# primobot.net
KiCad netlist of a schematic drawn in EAGLE
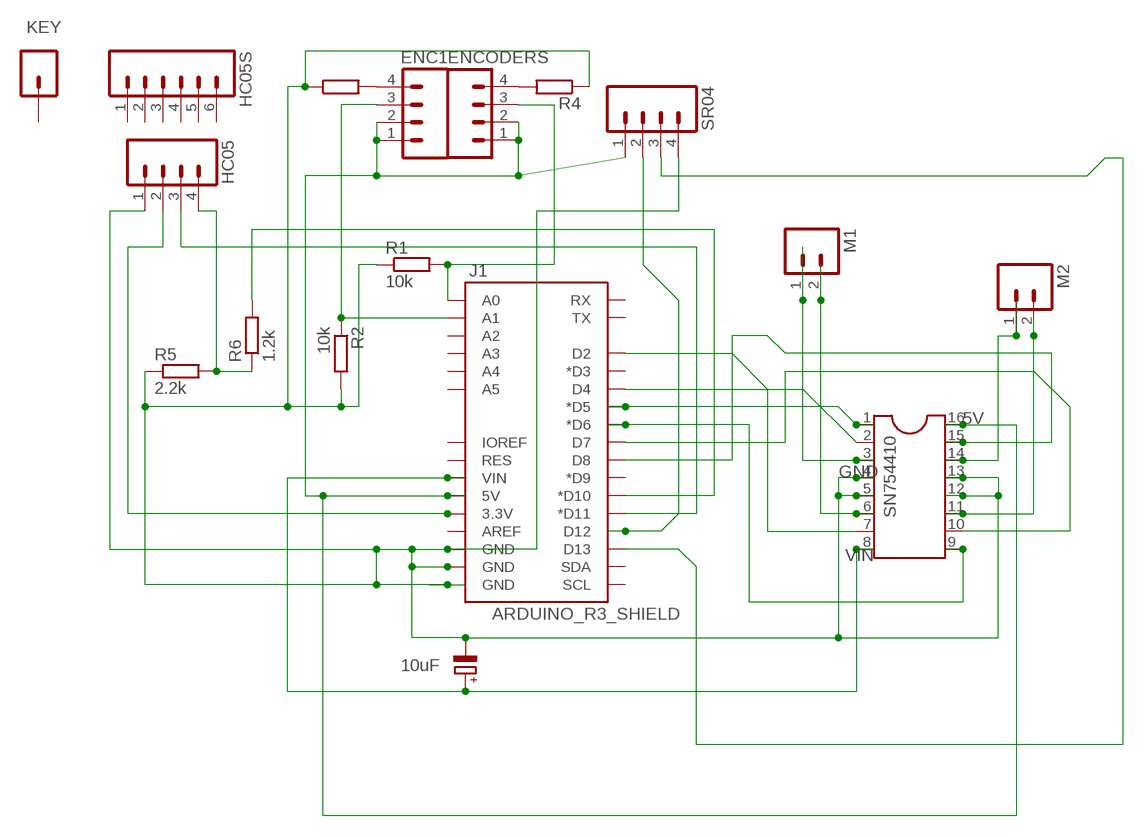
[diagram p0: schematic, sheet 1]

(export (version "E")
  (design (tool "Eeschema 10.0.6"))
  (components
    (comp (ref "C1")
      (value "10uF")
      (footprint "eagle-import:E5-10,5")
      (libsource (lib "eagle-import") (part "CPOL-EUE5-10.5"))
    )
    (comp (ref "ENC1")
      (value "M04PTH")
      (footprint "eagle-import:1X04")
      (libsource (lib "eagle-import") (part "M04PTH"))
    )
    (comp (ref "ENCODERS")
      (value "M04PTH")
      (footprint "eagle-import:1X04")
      (libsource (lib "eagle-import") (part "M04PTH"))
    )
    (comp (ref "HC05")
      (value "M04PTH")
      (footprint "eagle-import:1X04")
      (libsource (lib "eagle-import") (part "M04PTH"))
    )
    (comp (ref "HC05S")
      (value "M06SILK_FEMALE_PTH")
      (footprint "eagle-import:1X06")
      (libsource (lib "eagle-import") (part "M06SILK_FEMALE_PTH"))
    )
    (comp (ref "J1")
      (value "ARDUINO_R3_SHIELD")
      (footprint "eagle-import:UNO_R3_SHIELD")
      (libsource (lib "eagle-import") (part "ARDUINO_R3_SHIELD"))
    )
    (comp (ref "KEY")
      (value "M01PTH")
      (footprint "eagle-import:1X01")
      (libsource (lib "eagle-import") (part "M01PTH"))
    )
    (comp (ref "M1")
      (value "M02PTH")
      (footprint "eagle-import:1X02")
      (libsource (lib "eagle-import") (part "M02PTH"))
    )
    (comp (ref "M2")
      (value "M02PTH")
      (footprint "eagle-import:1X02")
      (libsource (lib "eagle-import") (part "M02PTH"))
    )
    (comp (ref "R1")
      (value "10k")
      (footprint "eagle-import:0207_10")
      (libsource (lib "eagle-import") (part "R-EU_0207/10"))
    )
    (comp (ref "R2")
      (value "10k")
      (footprint "eagle-import:0207_10")
      (libsource (lib "eagle-import") (part "R-EU_0207/10"))
    )
    (comp (ref "R3")
      (value "R-EU_0207/10")
      (footprint "eagle-import:0207_10")
      (libsource (lib "eagle-import") (part "R-EU_0207/10"))
    )
    (comp (ref "R4")
      (value "R-EU_0207/10")
      (footprint "eagle-import:0207_10")
      (libsource (lib "eagle-import") (part "R-EU_0207/10"))
    )
    (comp (ref "R5")
      (value "2.2k")
      (footprint "eagle-import:0207_10")
      (libsource (lib "eagle-import") (part "R-EU_0207/10"))
    )
    (comp (ref "R6")
      (value "1.2k")
      (footprint "eagle-import:0207_10")
      (libsource (lib "eagle-import") (part "R-EU_0207/10"))
    )
    (comp (ref "SN754410")
      (value "DIL16S")
      (footprint "eagle-import:SOCKET-16")
      (libsource (lib "eagle-import") (part "DIL16S"))
    )
    (comp (ref "SR04")
      (value "M04PTH")
      (footprint "eagle-import:1X04")
      (libsource (lib "eagle-import") (part "M04PTH"))
    )
  )
  (nets
    (net (code "1") (name "/5V") (class "Default")
      (node (ref "ENC1") (pin "1") (pinfunction "1_1") (pintype "passive"))
      (node (ref "ENC1") (pin "2") (pinfunction "2_2") (pintype "passive"))
      (node (ref "ENCODERS") (pin "1") (pinfunction "1_1") (pintype "passive"))
      (node (ref "ENCODERS") (pin "2") (pinfunction "2_2") (pintype "passive"))
      (node (ref "J1") (pin "5V") (pinfunction "5V_5V") (pintype "bidirectional"))
      (node (ref "SN754410") (pin "16") (pinfunction "16_16") (pintype "passive"))
      (node (ref "SR04") (pin "1") (pinfunction "1_1") (pintype "passive"))
    )
    (net (code "2") (name "/GND") (class "Default")
      (node (ref "C1") (pin "-") (pinfunction "-_-") (pintype "passive"))
      (node (ref "HC05") (pin "1") (pinfunction "1_1") (pintype "passive"))
      (node (ref "J1") (pin "GND@0") (pinfunction "GND_GND@0") (pintype "bidirectional"))
      (node (ref "J1") (pin "GND@1") (pinfunction "GND_GND@1") (pintype "bidirectional"))
      (node (ref "J1") (pin "GND@2") (pinfunction "GND_GND@2") (pintype "bidirectional"))
      (node (ref "R1") (pin "1") (pinfunction "1_1") (pintype "passive"))
      (node (ref "R2") (pin "2") (pinfunction "2_2") (pintype "passive"))
      (node (ref "R3") (pin "1") (pinfunction "1_1") (pintype "passive"))
      (node (ref "R4") (pin "1") (pinfunction "1_1") (pintype "passive"))
      (node (ref "R5") (pin "1") (pinfunction "1_1") (pintype "passive"))
      (node (ref "SN754410") (pin "12") (pinfunction "12_12") (pintype "passive"))
      (node (ref "SN754410") (pin "13") (pinfunction "13_13") (pintype "passive"))
      (node (ref "SN754410") (pin "4") (pinfunction "4_4") (pintype "passive"))
      (node (ref "SN754410") (pin "5") (pinfunction "5_5") (pintype "passive"))
      (node (ref "SR04") (pin "4") (pinfunction "4_4") (pintype "passive"))
    )
    (net (code "3") (name "/VIN") (class "Default")
      (node (ref "C1") (pin "+") (pinfunction "+_+") (pintype "passive"))
      (node (ref "J1") (pin "VIN") (pinfunction "VIN_VIN") (pintype "bidirectional"))
      (node (ref "SN754410") (pin "8") (pinfunction "8_8") (pintype "passive"))
    )
    (net (code "4") (name "Net-(ENC1-Pad3)") (class "Default")
      (node (ref "ENC1") (pin "3") (pinfunction "3_3") (pintype "passive"))
      (node (ref "J1") (pin "A1") (pinfunction "A1_A1") (pintype "bidirectional"))
      (node (ref "R2") (pin "1") (pinfunction "1_1") (pintype "passive"))
    )
    (net (code "5") (name "Net-(ENC1-Pad4)") (class "Default")
      (node (ref "ENC1") (pin "4") (pinfunction "4_4") (pintype "passive"))
      (node (ref "R3") (pin "2") (pinfunction "2_2") (pintype "passive"))
    )
    (net (code "6") (name "Net-(ENCODERS-Pad3)") (class "Default")
      (node (ref "ENCODERS") (pin "3") (pinfunction "3_3") (pintype "passive"))
      (node (ref "J1") (pin "A0") (pinfunction "A0_A0") (pintype "bidirectional"))
      (node (ref "R1") (pin "2") (pinfunction "2_2") (pintype "passive"))
    )
    (net (code "7") (name "Net-(ENCODERS-Pad4)") (class "Default")
      (node (ref "ENCODERS") (pin "4") (pinfunction "4_4") (pintype "passive"))
      (node (ref "R4") (pin "2") (pinfunction "2_2") (pintype "passive"))
    )
    (net (code "8") (name "Net-(HC05-Pad2)") (class "Default")
      (node (ref "HC05") (pin "2") (pinfunction "2_2") (pintype "passive"))
      (node (ref "J1") (pin "3.3V") (pinfunction "3.3V_3.3V") (pintype "bidirectional"))
    )
    (net (code "9") (name "Net-(HC05-Pad4)") (class "Default")
      (node (ref "HC05") (pin "4") (pinfunction "4_4") (pintype "passive"))
      (node (ref "R5") (pin "2") (pinfunction "2_2") (pintype "passive"))
      (node (ref "R6") (pin "1") (pinfunction "1_1") (pintype "passive"))
    )
    (net (code "10") (name "Net-(J1-*D5)") (class "Default")
      (node (ref "J1") (pin "D5") (pinfunction "*D5_D5") (pintype "bidirectional"))
      (node (ref "SN754410") (pin "1") (pinfunction "1_1") (pintype "passive"))
    )
    (net (code "11") (name "Net-(J1-*D6)") (class "Default")
      (node (ref "J1") (pin "D6") (pinfunction "*D6_D6") (pintype "bidirectional"))
      (node (ref "SN754410") (pin "9") (pinfunction "9_9") (pintype "passive"))
    )
    (net (code "12") (name "Net-(J1-*D10)") (class "Default")
      (node (ref "J1") (pin "D10") (pinfunction "*D10_D10") (pintype "bidirectional"))
      (node (ref "R6") (pin "2") (pinfunction "2_2") (pintype "passive"))
    )
    (net (code "13") (name "Net-(J1-*D11)") (class "Default")
      (node (ref "HC05") (pin "3") (pinfunction "3_3") (pintype "passive"))
      (node (ref "J1") (pin "D11") (pinfunction "*D11_D11") (pintype "bidirectional"))
    )
    (net (code "14") (name "Net-(J1-PadD2)") (class "Default")
      (node (ref "J1") (pin "D2") (pinfunction "D2_D2") (pintype "bidirectional"))
      (node (ref "SN754410") (pin "7") (pinfunction "7_7") (pintype "passive"))
    )
    (net (code "15") (name "Net-(J1-PadD4)") (class "Default")
      (node (ref "J1") (pin "D4") (pinfunction "D4_D4") (pintype "bidirectional"))
      (node (ref "SN754410") (pin "2") (pinfunction "2_2") (pintype "passive"))
    )
    (net (code "16") (name "Net-(J1-PadD7)") (class "Default")
      (node (ref "J1") (pin "D7") (pinfunction "D7_D7") (pintype "bidirectional"))
      (node (ref "SN754410") (pin "10") (pinfunction "10_10") (pintype "passive"))
    )
    (net (code "17") (name "Net-(J1-PadD8)") (class "Default")
      (node (ref "J1") (pin "D8") (pinfunction "D8_D8") (pintype "bidirectional"))
      (node (ref "SN754410") (pin "15") (pinfunction "15_15") (pintype "passive"))
    )
    (net (code "18") (name "Net-(J1-PadD12)") (class "Default")
      (node (ref "J1") (pin "D12") (pinfunction "D12_D12") (pintype "bidirectional"))
      (node (ref "SR04") (pin "2") (pinfunction "2_2") (pintype "passive"))
    )
    (net (code "19") (name "Net-(J1-PadD13)") (class "Default")
      (node (ref "J1") (pin "D13") (pinfunction "D13_D13") (pintype "bidirectional"))
      (node (ref "SR04") (pin "3") (pinfunction "3_3") (pintype "passive"))
    )
    (net (code "20") (name "Net-(M1-Pad1)") (class "Default")
      (node (ref "M1") (pin "1") (pinfunction "1_1") (pintype "passive"))
      (node (ref "SN754410") (pin "3") (pinfunction "3_3") (pintype "passive"))
    )
    (net (code "21") (name "Net-(M1-Pad2)") (class "Default")
      (node (ref "M1") (pin "2") (pinfunction "2_2") (pintype "passive"))
      (node (ref "SN754410") (pin "6") (pinfunction "6_6") (pintype "passive"))
    )
    (net (code "22") (name "Net-(M2-Pad1)") (class "Default")
      (node (ref "M2") (pin "1") (pinfunction "1_1") (pintype "passive"))
      (node (ref "SN754410") (pin "14") (pinfunction "14_14") (pintype "passive"))
    )
    (net (code "23") (name "Net-(M2-Pad2)") (class "Default")
      (node (ref "M2") (pin "2") (pinfunction "2_2") (pintype "passive"))
      (node (ref "SN754410") (pin "11") (pinfunction "11_11") (pintype "passive"))
    )
    (net (code "24") (name "unconnected-(HC05S-Pad1)") (class "Default")
      (node (ref "HC05S") (pin "1") (pinfunction "1_1") (pintype "passive"))
    )
    (net (code "25") (name "unconnected-(HC05S-Pad2)") (class "Default")
      (node (ref "HC05S") (pin "2") (pinfunction "2_2") (pintype "passive"))
    )
    (net (code "26") (name "unconnected-(HC05S-Pad3)") (class "Default")
      (node (ref "HC05S") (pin "3") (pinfunction "3_3") (pintype "passive"))
    )
    (net (code "27") (name "unconnected-(HC05S-Pad4)") (class "Default")
      (node (ref "HC05S") (pin "4") (pinfunction "4_4") (pintype "passive"))
    )
    (net (code "28") (name "unconnected-(HC05S-Pad5)") (class "Default")
      (node (ref "HC05S") (pin "5") (pinfunction "5_5") (pintype "passive"))
    )
    (net (code "29") (name "unconnected-(HC05S-Pad6)") (class "Default")
      (node (ref "HC05S") (pin "6") (pinfunction "6_6") (pintype "passive"))
    )
    (net (code "30") (name "unconnected-(J1-*D3-PadD3)") (class "Default")
      (node (ref "J1") (pin "D3") (pinfunction "*D3_D3") (pintype "bidirectional"))
    )
    (net (code "31") (name "unconnected-(J1-*D9-PadD9)") (class "Default")
      (node (ref "J1") (pin "D9") (pinfunction "*D9_D9") (pintype "bidirectional"))
    )
    (net (code "32") (name "unconnected-(J1-PadA2)") (class "Default")
      (node (ref "J1") (pin "A2") (pinfunction "A2_A2") (pintype "bidirectional"))
    )
    (net (code "33") (name "unconnected-(J1-PadA3)") (class "Default")
      (node (ref "J1") (pin "A3") (pinfunction "A3_A3") (pintype "bidirectional"))
    )
    (net (code "34") (name "unconnected-(J1-PadA4)") (class "Default")
      (node (ref "J1") (pin "A4") (pinfunction "A4_A4") (pintype "bidirectional"))
    )
    (net (code "35") (name "unconnected-(J1-PadA5)") (class "Default")
      (node (ref "J1") (pin "A5") (pinfunction "A5_A5") (pintype "bidirectional"))
    )
    (net (code "36") (name "unconnected-(J1-PadAREF)") (class "Default")
      (node (ref "J1") (pin "AREF") (pinfunction "AREF_AREF") (pintype "bidirectional"))
    )
    (net (code "37") (name "unconnected-(J1-PadIOREF)") (class "Default")
      (node (ref "J1") (pin "IOREF") (pinfunction "IOREF_IOREF") (pintype "bidirectional"))
    )
    (net (code "38") (name "unconnected-(J1-PadRES)") (class "Default")
      (node (ref "J1") (pin "RES") (pinfunction "RES_RES") (pintype "bidirectional"))
    )
    (net (code "39") (name "unconnected-(J1-PadRX)") (class "Default")
      (node (ref "J1") (pin "RX") (pinfunction "RX_RX") (pintype "bidirectional"))
    )
    (net (code "40") (name "unconnected-(J1-PadSCL)") (class "Default")
      (node (ref "J1") (pin "SCL") (pinfunction "SCL_SCL") (pintype "bidirectional"))
    )
    (net (code "41") (name "unconnected-(J1-PadSDA)") (class "Default")
      (node (ref "J1") (pin "SDA") (pinfunction "SDA_SDA") (pintype "bidirectional"))
    )
    (net (code "42") (name "unconnected-(J1-PadTX)") (class "Default")
      (node (ref "J1") (pin "TX") (pinfunction "TX_TX") (pintype "bidirectional"))
    )
    (net (code "43") (name "unconnected-(KEY-Pad1)") (class "Default")
      (node (ref "KEY") (pin "1") (pinfunction "1_1") (pintype "passive"))
    )
  )
)
